# DenScript_Arduino_Shield_V1_0.net
KiCad netlist of a schematic drawn in EAGLE
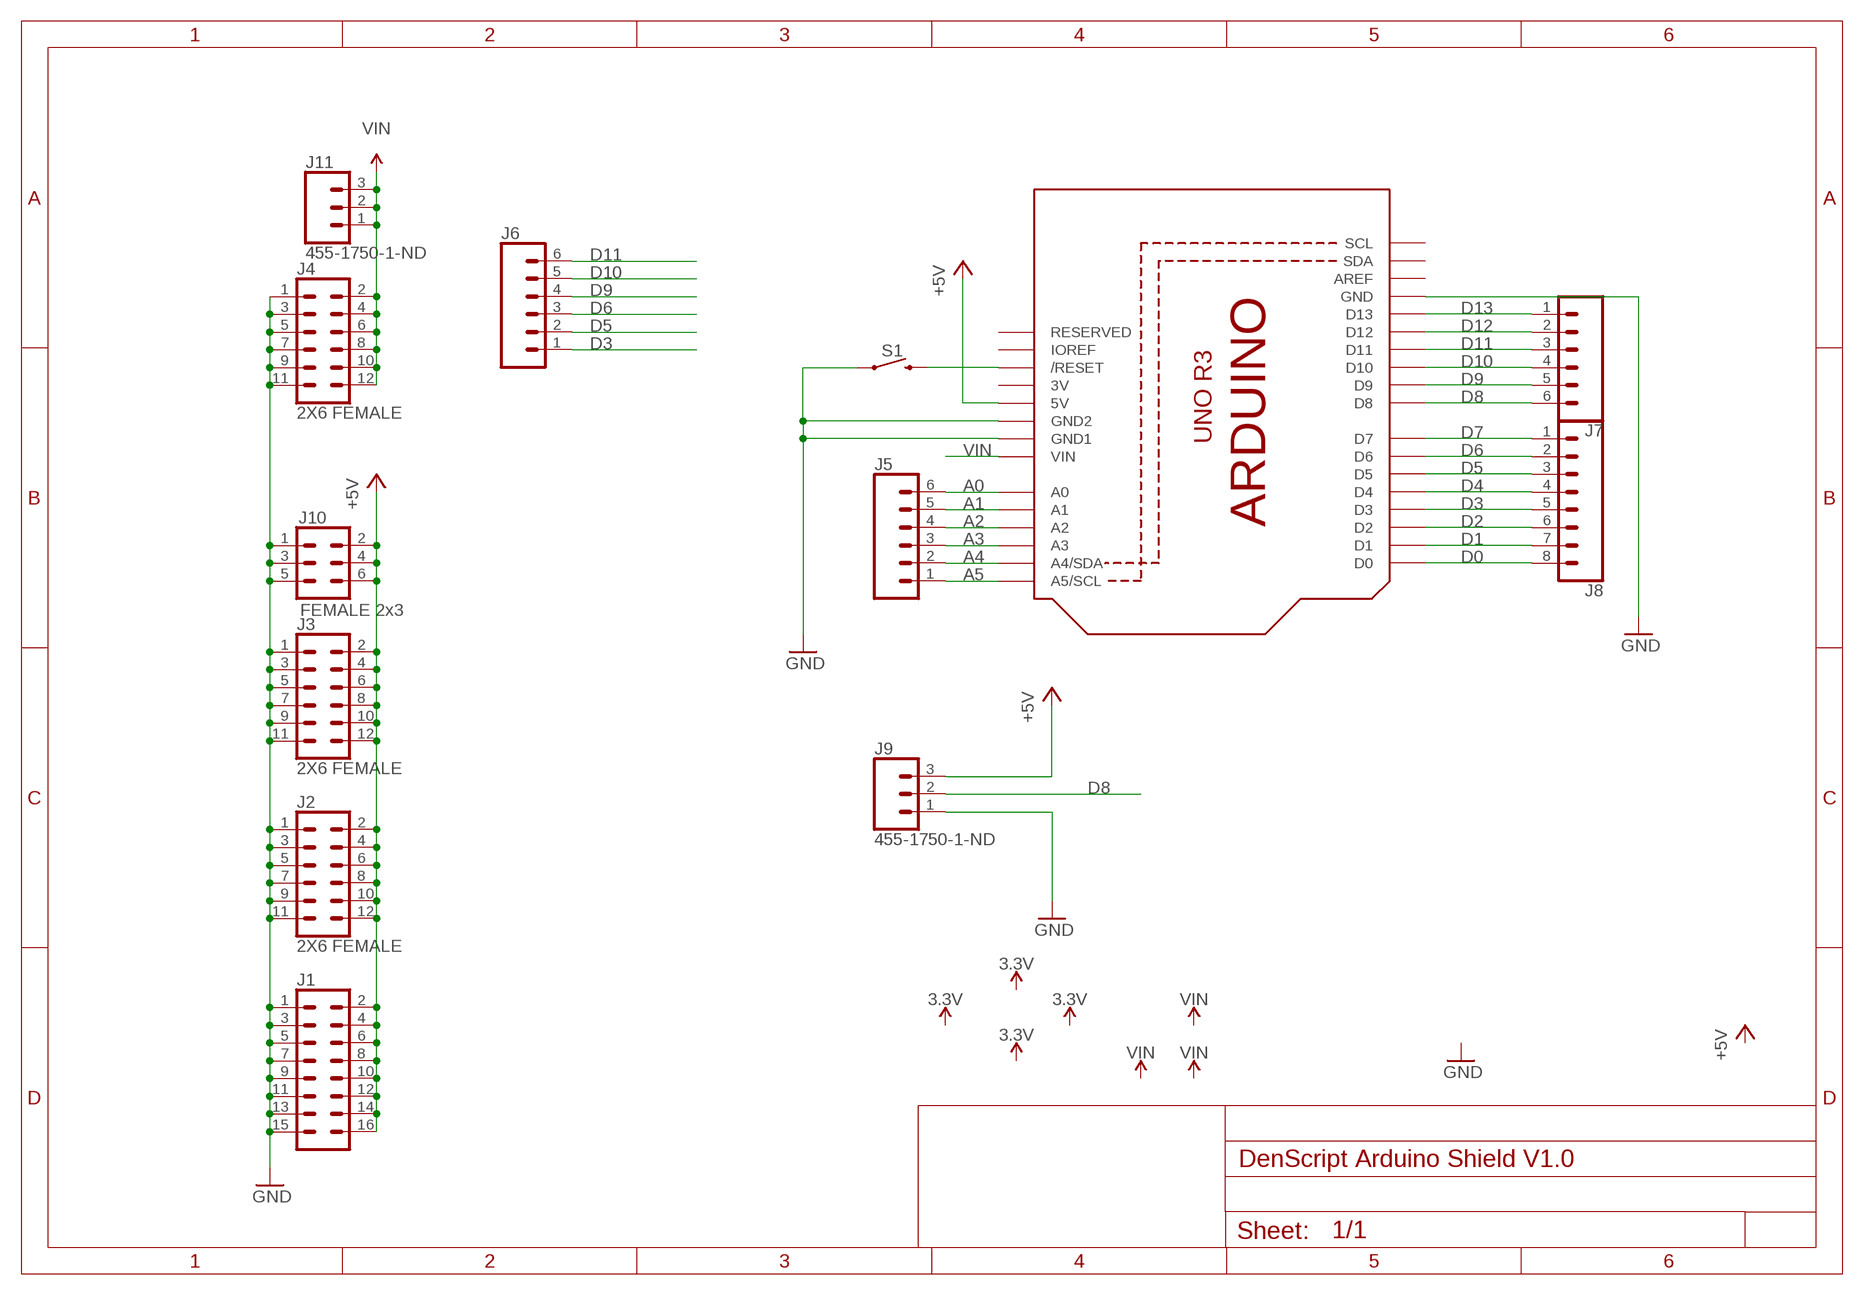
[diagram p0: schematic, sheet 1]

(export (version "E")
  (design (tool "Eeschema 10.0.6"))
  (components
    (comp (ref "J1")
      (value "CONN_08X2_HEADER")
      (footprint "eagle-import:2X8")
      (libsource (lib "eagle-import") (part "CONN_08X2_HEADER"))
    )
    (comp (ref "J2")
      (value "2X6 FEMALE")
      (footprint "eagle-import:2X6")
      (libsource (lib "eagle-import") (part "CONN_06X2PTH_FEMALE"))
    )
    (comp (ref "J3")
      (value "2X6 FEMALE")
      (footprint "eagle-import:2X6")
      (libsource (lib "eagle-import") (part "CONN_06X2PTH_FEMALE"))
    )
    (comp (ref "J4")
      (value "2X6 FEMALE")
      (footprint "eagle-import:2X6")
      (libsource (lib "eagle-import") (part "CONN_06X2PTH_FEMALE"))
    )
    (comp (ref "J5")
      (value "CONN_06SILK_FEMALE_PTH")
      (footprint "eagle-import:1X06")
      (libsource (lib "eagle-import") (part "CONN_06SILK_FEMALE_PTH"))
    )
    (comp (ref "J6")
      (value "CONN_06SILK_FEMALE_PTH")
      (footprint "eagle-import:1X06")
      (libsource (lib "eagle-import") (part "CONN_06SILK_FEMALE_PTH"))
    )
    (comp (ref "J7")
      (value "CONN_06SILK_FEMALE_PTH")
      (footprint "eagle-import:1X06")
      (libsource (lib "eagle-import") (part "CONN_06SILK_FEMALE_PTH"))
    )
    (comp (ref "J8")
      (value "CONN_08\"")
      (footprint "eagle-import:1X08")
      (libsource (lib "eagle-import") (part "CONN_08{dblquote}"))
    )
    (comp (ref "J9")
      (value "455-1750-1-ND")
      (footprint "eagle-import:1X03")
      (libsource (lib "eagle-import") (part "CONN_03"))
    )
    (comp (ref "J10")
      (value "FEMALE 2x3")
      (footprint "eagle-import:2X3")
      (libsource (lib "eagle-import") (part "CONN_03X2FEMALE"))
    )
    (comp (ref "J11")
      (value "455-1750-1-ND")
      (footprint "eagle-import:1X03")
      (libsource (lib "eagle-import") (part "CONN_03"))
    )
    (comp (ref "S1")
      (value "MOMENTARY-SWITCH-SPST-PTH-6.0MM")
      (footprint "eagle-import:TACTILE_SWITCH_PTH_6.0MM")
      (libsource (lib "eagle-import") (part "MOMENTARY-SWITCH-SPST-PTH-6.0MM"))
    )
    (comp (ref "U1")
      (value "ARDUINOR3-BPLACE")
      (footprint "eagle-import:ARDUINOR3-BPLACE")
      (libsource (lib "eagle-import") (part "ARDUINOR3-BPLACE"))
    )
  )
  (nets
    (net (code "1") (name "+5V") (class "Default")
      (node (ref "J1") (pin "10") (pinfunction "10_10") (pintype "passive"))
      (node (ref "J1") (pin "12") (pinfunction "12_12") (pintype "passive"))
      (node (ref "J1") (pin "14") (pinfunction "14_14") (pintype "passive"))
      (node (ref "J1") (pin "16") (pinfunction "16_16") (pintype "passive"))
      (node (ref "J1") (pin "2") (pinfunction "2_2") (pintype "passive"))
      (node (ref "J1") (pin "4") (pinfunction "4_4") (pintype "passive"))
      (node (ref "J1") (pin "6") (pinfunction "6_6") (pintype "passive"))
      (node (ref "J1") (pin "8") (pinfunction "8_8") (pintype "passive"))
      (node (ref "J10") (pin "2") (pinfunction "2_2") (pintype "bidirectional"))
      (node (ref "J10") (pin "4") (pinfunction "4_4") (pintype "bidirectional"))
      (node (ref "J10") (pin "6") (pinfunction "6_6") (pintype "bidirectional"))
      (node (ref "J2") (pin "10") (pinfunction "10_10") (pintype "passive"))
      (node (ref "J2") (pin "12") (pinfunction "12_12") (pintype "passive"))
      (node (ref "J2") (pin "2") (pinfunction "2_2") (pintype "passive"))
      (node (ref "J2") (pin "4") (pinfunction "4_4") (pintype "passive"))
      (node (ref "J2") (pin "6") (pinfunction "6_6") (pintype "passive"))
      (node (ref "J2") (pin "8") (pinfunction "8_8") (pintype "passive"))
      (node (ref "J3") (pin "10") (pinfunction "10_10") (pintype "passive"))
      (node (ref "J3") (pin "12") (pinfunction "12_12") (pintype "passive"))
      (node (ref "J3") (pin "2") (pinfunction "2_2") (pintype "passive"))
      (node (ref "J3") (pin "4") (pinfunction "4_4") (pintype "passive"))
      (node (ref "J3") (pin "6") (pinfunction "6_6") (pintype "passive"))
      (node (ref "J3") (pin "8") (pinfunction "8_8") (pintype "passive"))
      (node (ref "J9") (pin "3") (pinfunction "3_3") (pintype "passive"))
      (node (ref "U1") (pin "5V") (pinfunction "5V_5V") (pintype "power_in"))
    )
    (net (code "2") (name "/3V") (class "Default")
      (node (ref "U1") (pin "3V") (pinfunction "3V_3V") (pintype "power_in"))
    )
    (net (code "3") (name "/A0") (class "Default")
      (node (ref "J5") (pin "6") (pinfunction "6_6") (pintype "passive"))
      (node (ref "U1") (pin "A0") (pinfunction "A0_A0") (pintype "bidirectional"))
    )
    (net (code "4") (name "/A1") (class "Default")
      (node (ref "J5") (pin "5") (pinfunction "5_5") (pintype "passive"))
      (node (ref "U1") (pin "A1") (pinfunction "A1_A1") (pintype "bidirectional"))
    )
    (net (code "5") (name "/A2") (class "Default")
      (node (ref "J5") (pin "4") (pinfunction "4_4") (pintype "passive"))
      (node (ref "U1") (pin "A2") (pinfunction "A2_A2") (pintype "bidirectional"))
    )
    (net (code "6") (name "/A3") (class "Default")
      (node (ref "J5") (pin "3") (pinfunction "3_3") (pintype "passive"))
      (node (ref "U1") (pin "A3") (pinfunction "A3_A3") (pintype "bidirectional"))
    )
    (net (code "7") (name "/A4") (class "Default")
      (node (ref "J5") (pin "2") (pinfunction "2_2") (pintype "passive"))
      (node (ref "U1") (pin "A4") (pinfunction "A4/SDA_A4") (pintype "bidirectional"))
    )
    (net (code "8") (name "/A5") (class "Default")
      (node (ref "J5") (pin "1") (pinfunction "1_1") (pintype "passive"))
      (node (ref "U1") (pin "A5") (pinfunction "A5/SCL_A5") (pintype "bidirectional"))
    )
    (net (code "9") (name "/D0") (class "Default")
      (node (ref "J8") (pin "8") (pinfunction "8_8") (pintype "passive"))
      (node (ref "U1") (pin "D0") (pinfunction "D0_D0") (pintype "bidirectional"))
    )
    (net (code "10") (name "/D1") (class "Default")
      (node (ref "J8") (pin "7") (pinfunction "7_7") (pintype "passive"))
      (node (ref "U1") (pin "D1") (pinfunction "D1_D1") (pintype "bidirectional"))
    )
    (net (code "11") (name "/D2") (class "Default")
      (node (ref "J8") (pin "6") (pinfunction "6_6") (pintype "passive"))
      (node (ref "U1") (pin "D2") (pinfunction "D2_D2") (pintype "bidirectional"))
    )
    (net (code "12") (name "/D3") (class "Default")
      (node (ref "J6") (pin "1") (pinfunction "1_1") (pintype "passive"))
      (node (ref "J8") (pin "5") (pinfunction "5_5") (pintype "passive"))
      (node (ref "U1") (pin "D3") (pinfunction "D3_D3") (pintype "bidirectional"))
    )
    (net (code "13") (name "/D4") (class "Default")
      (node (ref "J8") (pin "4") (pinfunction "4_4") (pintype "passive"))
      (node (ref "U1") (pin "D4") (pinfunction "D4_D4") (pintype "bidirectional"))
    )
    (net (code "14") (name "/D5") (class "Default")
      (node (ref "J6") (pin "2") (pinfunction "2_2") (pintype "passive"))
      (node (ref "J8") (pin "3") (pinfunction "3_3") (pintype "passive"))
      (node (ref "U1") (pin "D5") (pinfunction "D5_D5") (pintype "bidirectional"))
    )
    (net (code "15") (name "/D6") (class "Default")
      (node (ref "J6") (pin "3") (pinfunction "3_3") (pintype "passive"))
      (node (ref "J8") (pin "2") (pinfunction "2_2") (pintype "passive"))
      (node (ref "U1") (pin "D6") (pinfunction "D6_D6") (pintype "bidirectional"))
    )
    (net (code "16") (name "/D7") (class "Default")
      (node (ref "J8") (pin "1") (pinfunction "1_1") (pintype "passive"))
      (node (ref "U1") (pin "D7") (pinfunction "D7_D7") (pintype "bidirectional"))
    )
    (net (code "17") (name "/D8") (class "Default")
      (node (ref "J7") (pin "6") (pinfunction "6_6") (pintype "passive"))
      (node (ref "J9") (pin "2") (pinfunction "2_2") (pintype "passive"))
      (node (ref "U1") (pin "D8") (pinfunction "D8_D8") (pintype "bidirectional"))
    )
    (net (code "18") (name "/D9") (class "Default")
      (node (ref "J6") (pin "4") (pinfunction "4_4") (pintype "passive"))
      (node (ref "J7") (pin "5") (pinfunction "5_5") (pintype "passive"))
      (node (ref "U1") (pin "D9") (pinfunction "D9_D9") (pintype "bidirectional"))
    )
    (net (code "19") (name "/D10") (class "Default")
      (node (ref "J6") (pin "5") (pinfunction "5_5") (pintype "passive"))
      (node (ref "J7") (pin "4") (pinfunction "4_4") (pintype "passive"))
      (node (ref "U1") (pin "D10") (pinfunction "D10_D10") (pintype "bidirectional"))
    )
    (net (code "20") (name "/D11") (class "Default")
      (node (ref "J6") (pin "6") (pinfunction "6_6") (pintype "passive"))
      (node (ref "J7") (pin "3") (pinfunction "3_3") (pintype "passive"))
      (node (ref "U1") (pin "D11") (pinfunction "D11_D11") (pintype "bidirectional"))
    )
    (net (code "21") (name "/D12") (class "Default")
      (node (ref "J7") (pin "2") (pinfunction "2_2") (pintype "passive"))
      (node (ref "U1") (pin "D12") (pinfunction "D12_D12") (pintype "bidirectional"))
    )
    (net (code "22") (name "/D13") (class "Default")
      (node (ref "J7") (pin "1") (pinfunction "1_1") (pintype "passive"))
      (node (ref "U1") (pin "D13") (pinfunction "D13_D13") (pintype "bidirectional"))
    )
    (net (code "24") (name "GND") (class "Default")
      (node (ref "J1") (pin "1") (pinfunction "1_1") (pintype "passive"))
      (node (ref "J1") (pin "11") (pinfunction "11_11") (pintype "passive"))
      (node (ref "J1") (pin "13") (pinfunction "13_13") (pintype "passive"))
      (node (ref "J1") (pin "15") (pinfunction "15_15") (pintype "passive"))
      (node (ref "J1") (pin "3") (pinfunction "3_3") (pintype "passive"))
      (node (ref "J1") (pin "5") (pinfunction "5_5") (pintype "passive"))
      (node (ref "J1") (pin "7") (pinfunction "7_7") (pintype "passive"))
      (node (ref "J1") (pin "9") (pinfunction "9_9") (pintype "passive"))
      (node (ref "J10") (pin "1") (pinfunction "1_1") (pintype "bidirectional"))
      (node (ref "J10") (pin "3") (pinfunction "3_3") (pintype "bidirectional"))
      (node (ref "J10") (pin "5") (pinfunction "5_5") (pintype "bidirectional"))
      (node (ref "J2") (pin "1") (pinfunction "1_1") (pintype "passive"))
      (node (ref "J2") (pin "11") (pinfunction "11_11") (pintype "passive"))
      (node (ref "J2") (pin "3") (pinfunction "3_3") (pintype "passive"))
      (node (ref "J2") (pin "5") (pinfunction "5_5") (pintype "passive"))
      (node (ref "J2") (pin "7") (pinfunction "7_7") (pintype "passive"))
      (node (ref "J2") (pin "9") (pinfunction "9_9") (pintype "passive"))
      (node (ref "J3") (pin "1") (pinfunction "1_1") (pintype "passive"))
      (node (ref "J3") (pin "11") (pinfunction "11_11") (pintype "passive"))
      (node (ref "J3") (pin "3") (pinfunction "3_3") (pintype "passive"))
      (node (ref "J3") (pin "5") (pinfunction "5_5") (pintype "passive"))
      (node (ref "J3") (pin "7") (pinfunction "7_7") (pintype "passive"))
      (node (ref "J3") (pin "9") (pinfunction "9_9") (pintype "passive"))
      (node (ref "J4") (pin "1") (pinfunction "1_1") (pintype "passive"))
      (node (ref "J4") (pin "11") (pinfunction "11_11") (pintype "passive"))
      (node (ref "J4") (pin "3") (pinfunction "3_3") (pintype "passive"))
      (node (ref "J4") (pin "5") (pinfunction "5_5") (pintype "passive"))
      (node (ref "J4") (pin "7") (pinfunction "7_7") (pintype "passive"))
      (node (ref "J4") (pin "9") (pinfunction "9_9") (pintype "passive"))
      (node (ref "J9") (pin "1") (pinfunction "1_1") (pintype "passive"))
      (node (ref "S1") (pin "1") (pinfunction "1_1") (pintype "passive"))
      (node (ref "U1") (pin "GND") (pinfunction "GND_GND") (pintype "power_in"))
      (node (ref "U1") (pin "GND1") (pinfunction "GND1_GND1") (pintype "power_in"))
      (node (ref "U1") (pin "GND2") (pinfunction "GND2_GND2") (pintype "power_in"))
    )
    (net (code "25") (name "Net-(S1-2)") (class "Default")
      (node (ref "S1") (pin "3") (pinfunction "2_3") (pintype "passive"))
      (node (ref "U1") (pin "RESET") (pinfunction "/RESET_RESET") (pintype "bidirectional"))
    )
    (net (code "26") (name "VIN") (class "Default")
      (node (ref "J11") (pin "1") (pinfunction "1_1") (pintype "passive"))
      (node (ref "J11") (pin "2") (pinfunction "2_2") (pintype "passive"))
      (node (ref "J11") (pin "3") (pinfunction "3_3") (pintype "passive"))
      (node (ref "J4") (pin "10") (pinfunction "10_10") (pintype "passive"))
      (node (ref "J4") (pin "12") (pinfunction "12_12") (pintype "passive"))
      (node (ref "J4") (pin "2") (pinfunction "2_2") (pintype "passive"))
      (node (ref "J4") (pin "4") (pinfunction "4_4") (pintype "passive"))
      (node (ref "J4") (pin "6") (pinfunction "6_6") (pintype "passive"))
      (node (ref "J4") (pin "8") (pinfunction "8_8") (pintype "passive"))
      (node (ref "U1") (pin "VIN") (pinfunction "VIN_VIN") (pintype "power_in"))
    )
    (net (code "27") (name "unconnected-(U1-PadAREF)") (class "Default")
      (node (ref "U1") (pin "AREF") (pinfunction "AREF_AREF") (pintype "bidirectional"))
    )
    (net (code "28") (name "unconnected-(U1-PadIOREF)") (class "Default")
      (node (ref "U1") (pin "IOREF") (pinfunction "IOREF_IOREF") (pintype "output"))
    )
    (net (code "29") (name "unconnected-(U1-PadRESERVED)") (class "Default")
      (node (ref "U1") (pin "RESERVED") (pinfunction "RESERVED_RESERVED") (pintype "no_connect"))
    )
    (net (code "30") (name "unconnected-(U1-PadSCL)") (class "Default")
      (node (ref "U1") (pin "SCL") (pinfunction "SCL_SCL") (pintype "bidirectional"))
    )
    (net (code "31") (name "unconnected-(U1-PadSDA)") (class "Default")
      (node (ref "U1") (pin "SDA") (pinfunction "SDA_SDA") (pintype "bidirectional"))
    )
  )
)
